# Adafruit_Feather_M0_Basic_rev_C.net
KiCad netlist of a schematic drawn in EAGLE
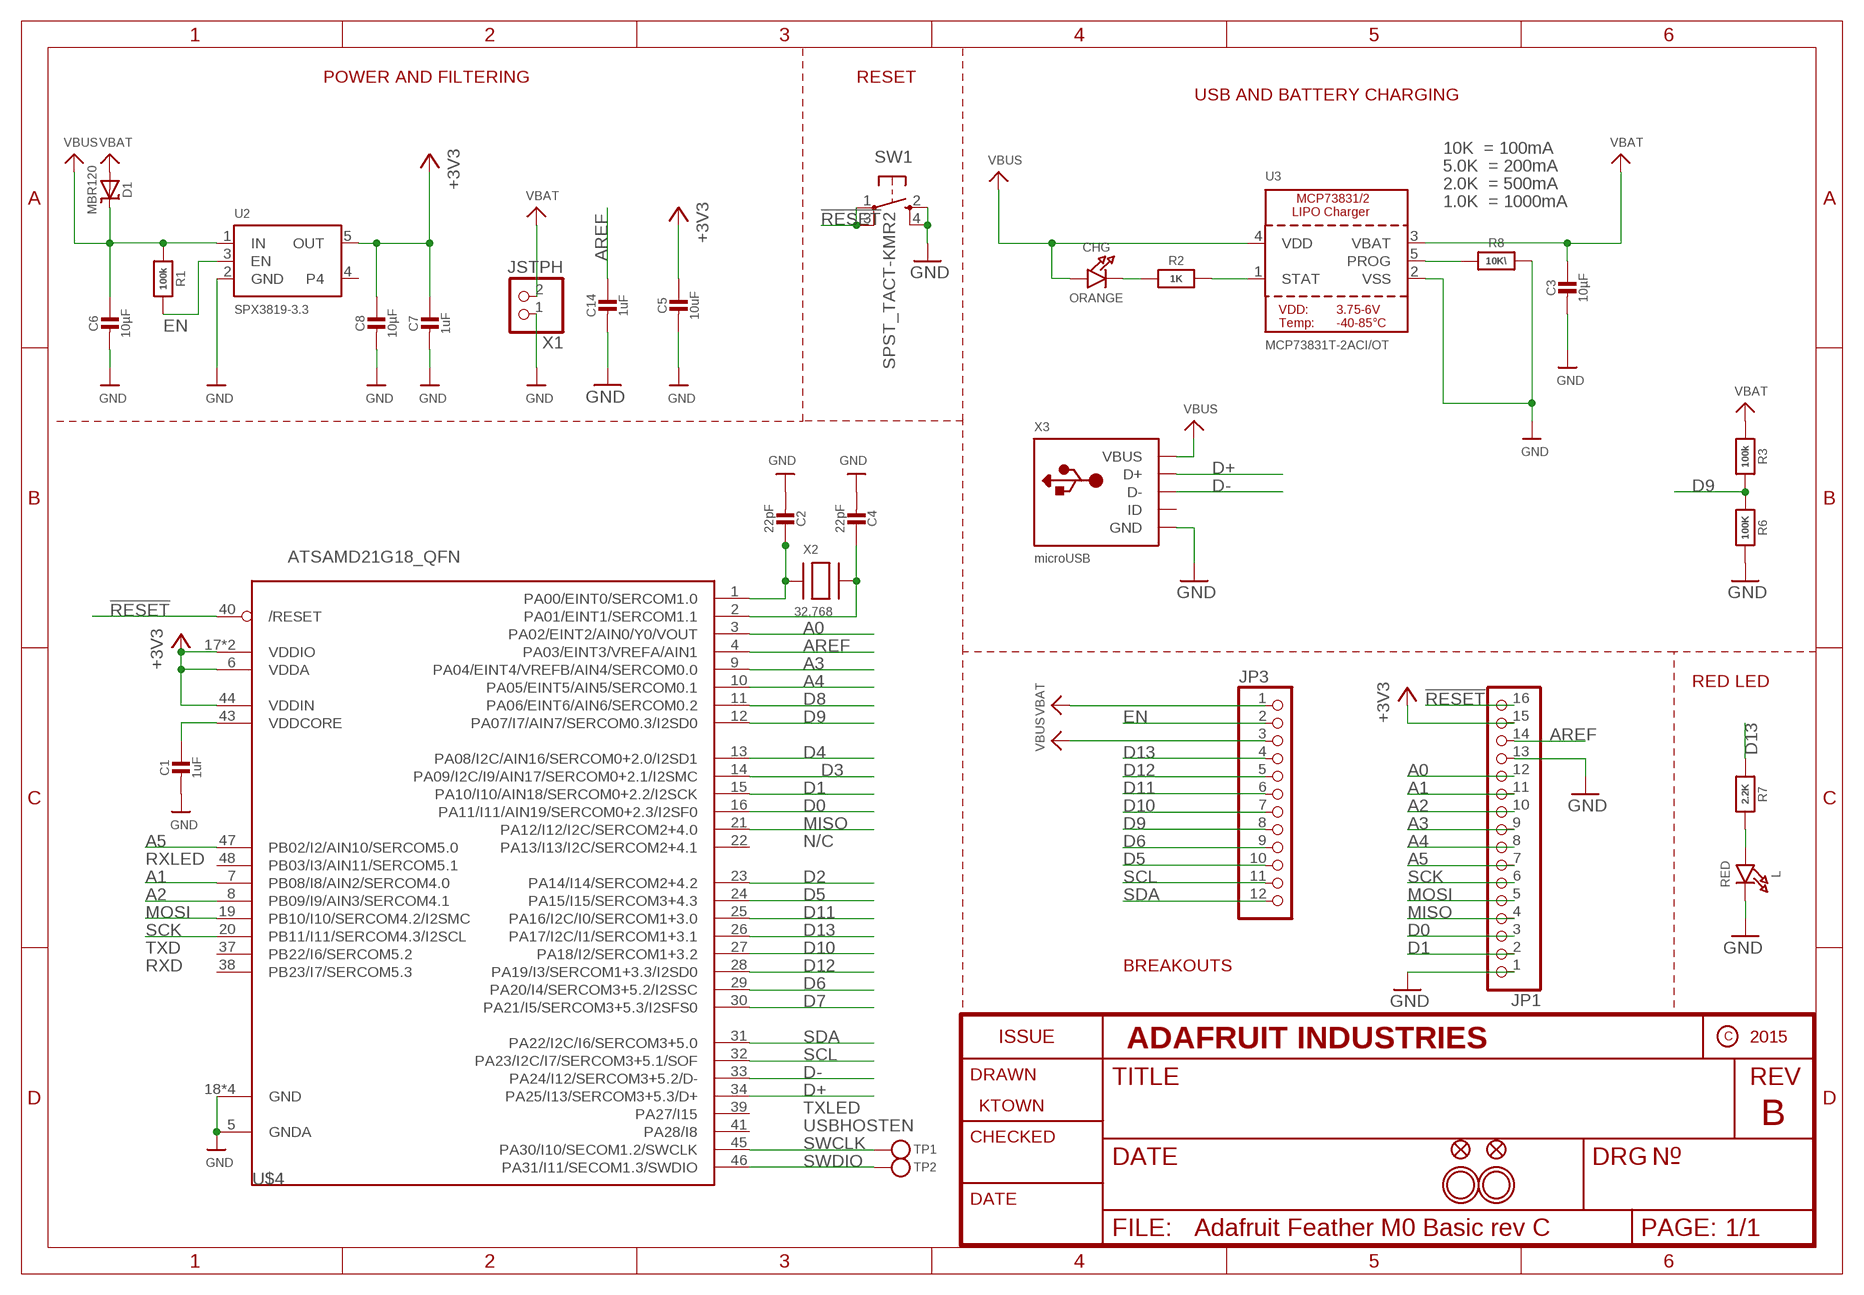
[diagram p0: schematic, sheet 1]

(export (version "E")
  (design (tool "Eeschema 10.0.6"))
  (components
    (comp (ref "C1")
      (value "1uF")
      (footprint "eagle-import:0603-NO")
      (libsource (lib "eagle-import") (part "CAP_CERAMIC0603_NO"))
    )
    (comp (ref "C2")
      (value "22pF")
      (footprint "eagle-import:0603-NO")
      (libsource (lib "eagle-import") (part "CAP_CERAMIC0603_NO"))
    )
    (comp (ref "C3")
      (value "10µF")
      (footprint "eagle-import:0805-NO")
      (libsource (lib "eagle-import") (part "CAP_CERAMIC0805-NOOUTLINE"))
    )
    (comp (ref "C4")
      (value "22pF")
      (footprint "eagle-import:0603-NO")
      (libsource (lib "eagle-import") (part "CAP_CERAMIC0603_NO"))
    )
    (comp (ref "C5")
      (value "10uF")
      (footprint "eagle-import:0805-NO")
      (libsource (lib "eagle-import") (part "CAP_CERAMIC0805-NOOUTLINE"))
    )
    (comp (ref "C6")
      (value "10µF")
      (footprint "eagle-import:0805-NO")
      (libsource (lib "eagle-import") (part "CAP_CERAMIC0805-NOOUTLINE"))
    )
    (comp (ref "C7")
      (value "1uF")
      (footprint "eagle-import:0603-NO")
      (libsource (lib "eagle-import") (part "CAP_CERAMIC0603_NO"))
    )
    (comp (ref "C8")
      (value "10µF")
      (footprint "eagle-import:0805-NO")
      (libsource (lib "eagle-import") (part "CAP_CERAMIC0805-NOOUTLINE"))
    )
    (comp (ref "C14")
      (value "1uF")
      (footprint "eagle-import:0603-NO")
      (libsource (lib "eagle-import") (part "CAP_CERAMIC0603_NO"))
    )
    (comp (ref "CHG")
      (value "ORANGE")
      (footprint "eagle-import:CHIPLED_0805_NOOUTLINE")
      (libsource (lib "eagle-import") (part "LED0805_NOOUTLINE"))
    )
    (comp (ref "D1")
      (value "MBR120")
      (footprint "eagle-import:SOD-123")
      (libsource (lib "eagle-import") (part "DIODE-SCHOTTKYSOD-123"))
    )
    (comp (ref "JP1")
      (value "HEADER-1X16ROUND")
      (footprint "eagle-import:1X16_ROUND")
      (libsource (lib "eagle-import") (part "HEADER-1X16ROUND"))
    )
    (comp (ref "JP3")
      (value "HEADER-1X12")
      (footprint "eagle-import:1X12_ROUND")
      (libsource (lib "eagle-import") (part "HEADER-1X12"))
    )
    (comp (ref "L")
      (value "RED")
      (footprint "eagle-import:CHIPLED_0805_NOOUTLINE")
      (libsource (lib "eagle-import") (part "LED0805_NOOUTLINE"))
    )
    (comp (ref "R1")
      (value "100k")
      (footprint "eagle-import:0603-NO")
      (libsource (lib "eagle-import") (part "RESISTOR_0603_NOOUT"))
    )
    (comp (ref "R2")
      (value "1K")
      (footprint "eagle-import:0603-NO")
      (libsource (lib "eagle-import") (part "RESISTOR_0603_NOOUT"))
    )
    (comp (ref "R3")
      (value "100k")
      (footprint "eagle-import:0603-NO")
      (libsource (lib "eagle-import") (part "RESISTOR_0603_NOOUT"))
    )
    (comp (ref "R6")
      (value "100K")
      (footprint "eagle-import:0603-NO")
      (libsource (lib "eagle-import") (part "RESISTOR_0603_NOOUT"))
    )
    (comp (ref "R7")
      (value "2.2K")
      (footprint "eagle-import:0603-NO")
      (libsource (lib "eagle-import") (part "RESISTOR_0603_NOOUT"))
    )
    (comp (ref "R8")
      (value "10K\\")
      (footprint "eagle-import:0603-NO")
      (libsource (lib "eagle-import") (part "RESISTOR_0603_NOOUT"))
    )
    (comp (ref "SW1")
      (value "SPST_TACT-KMR2")
      (footprint "eagle-import:KMR2")
      (libsource (lib "eagle-import") (part "SPST_TACT-KMR2"))
    )
    (comp (ref "TP1")
      (value "TESTPOINTROUND1.5MM")
      (footprint "eagle-import:TESTPOINT_ROUND_1.5MM")
      (libsource (lib "eagle-import") (part "TESTPOINTROUND1.5MM"))
    )
    (comp (ref "TP2")
      (value "TESTPOINTROUND1.5MM")
      (footprint "eagle-import:TESTPOINT_ROUND_1.5MM")
      (libsource (lib "eagle-import") (part "TESTPOINTROUND1.5MM"))
    )
    (comp (ref "U$4")
      (value "ATSAMD21G18_QFN")
      (footprint "eagle-import:TQFN48_7MM")
      (libsource (lib "eagle-import") (part "ATSAMD21J_QFN"))
    )
    (comp (ref "U$31")
      (value "MOUNTINGHOLE2.5")
      (footprint "eagle-import:MOUNTINGHOLE_2.5_PLATED")
      (libsource (lib "eagle-import") (part "MOUNTINGHOLE2.5"))
    )
    (comp (ref "U$32")
      (value "MOUNTINGHOLE2.5")
      (footprint "eagle-import:MOUNTINGHOLE_2.5_PLATED")
      (libsource (lib "eagle-import") (part "MOUNTINGHOLE2.5"))
    )
    (comp (ref "U$34")
      (value "FIDUCIAL\"\"")
      (footprint "eagle-import:FIDUCIAL_1MM")
      (libsource (lib "eagle-import") (part "FIDUCIAL{dblquote}{dblquote}"))
    )
    (comp (ref "U$35")
      (value "FIDUCIAL\"\"")
      (footprint "eagle-import:FIDUCIAL_1MM")
      (libsource (lib "eagle-import") (part "FIDUCIAL{dblquote}{dblquote}"))
    )
    (comp (ref "U2")
      (value "SPX3819-3.3")
      (footprint "eagle-import:SOT23-5")
      (libsource (lib "eagle-import") (part "VREG_SOT23-5"))
    )
    (comp (ref "U3")
      (value "MCP73831T-2ACI/OT")
      (footprint "eagle-import:SOT23-5")
      (libsource (lib "eagle-import") (part "MCP73831/2"))
    )
    (comp (ref "X1")
      (value "JSTPH")
      (footprint "eagle-import:JSTPH2")
      (libsource (lib "eagle-import") (part "CON_JST_PH_2PIN"))
    )
    (comp (ref "X2")
      (value "32.768")
      (footprint "eagle-import:XTAL3215")
      (libsource (lib "eagle-import") (part "XTAL-3.2X1.5"))
    )
    (comp (ref "X3")
      (value "microUSB")
      (footprint "eagle-import:4UCONN_20329_V2")
      (libsource (lib "eagle-import") (part "USB_MICRO_20329_V2"))
    )
  )
  (nets
    (net (code "1") (name "+3V3") (class "Default")
      (node (ref "C5") (pin "1") (pinfunction "1_1") (pintype "passive"))
      (node (ref "C7") (pin "1") (pinfunction "1_1") (pintype "passive"))
      (node (ref "C8") (pin "1") (pinfunction "1_1") (pintype "passive"))
      (node (ref "JP1") (pin "15") (pinfunction "15_15") (pintype "passive"))
      (node (ref "U$4") (pin "17") (pinfunction "VDDIO_17") (pintype "power_in"))
      (node (ref "U$4") (pin "36") (pinfunction "VDDIO_36") (pintype "power_in"))
      (node (ref "U$4") (pin "44") (pinfunction "VDDIN_44") (pintype "power_in"))
      (node (ref "U$4") (pin "6") (pinfunction "VDDA_6") (pintype "power_in"))
      (node (ref "U2") (pin "5") (pinfunction "OUT_5") (pintype "power_in"))
    )
    (net (code "2") (name "/A0") (class "Default")
      (node (ref "JP1") (pin "12") (pinfunction "12_12") (pintype "passive"))
      (node (ref "U$4") (pin "3") (pinfunction "PA02/EINT2/AIN0/Y0/VOUT_3") (pintype "bidirectional"))
    )
    (net (code "3") (name "/A1") (class "Default")
      (node (ref "JP1") (pin "11") (pinfunction "11_11") (pintype "passive"))
      (node (ref "U$4") (pin "7") (pinfunction "PB08/I8/AIN2/SERCOM4.0_7") (pintype "bidirectional"))
    )
    (net (code "4") (name "/A2") (class "Default")
      (node (ref "JP1") (pin "10") (pinfunction "10_10") (pintype "passive"))
      (node (ref "U$4") (pin "8") (pinfunction "PB09/I9/AIN3/SERCOM4.1_8") (pintype "bidirectional"))
    )
    (net (code "5") (name "/A3") (class "Default")
      (node (ref "JP1") (pin "9") (pinfunction "9_9") (pintype "passive"))
      (node (ref "U$4") (pin "9") (pinfunction "PA04/EINT4/VREFB/AIN4/SERCOM0.0_9") (pintype "bidirectional"))
    )
    (net (code "6") (name "/A4") (class "Default")
      (node (ref "JP1") (pin "8") (pinfunction "8_8") (pintype "passive"))
      (node (ref "U$4") (pin "10") (pinfunction "PA05/EINT5/AIN5/SERCOM0.1_10") (pintype "bidirectional"))
    )
    (net (code "7") (name "/A5") (class "Default")
      (node (ref "JP1") (pin "7") (pinfunction "7_7") (pintype "passive"))
      (node (ref "U$4") (pin "47") (pinfunction "PB02/I2/AIN10/SERCOM5.0_47") (pintype "bidirectional"))
    )
    (net (code "8") (name "/AREF") (class "Default")
      (node (ref "C14") (pin "1") (pinfunction "1_1") (pintype "passive"))
      (node (ref "JP1") (pin "14") (pinfunction "14_14") (pintype "passive"))
      (node (ref "U$4") (pin "4") (pinfunction "PA03/EINT3/VREFA/AIN1_4") (pintype "bidirectional"))
    )
    (net (code "9") (name "/D+") (class "Default")
      (node (ref "U$4") (pin "34") (pinfunction "PA25/I13/SERCOM3+5.3/D+_34") (pintype "bidirectional"))
      (node (ref "X3") (pin "D+") (pinfunction "D+_D+") (pintype "bidirectional"))
    )
    (net (code "10") (name "/D-") (class "Default")
      (node (ref "U$4") (pin "33") (pinfunction "PA24/I12/SERCOM3+5.2/D-_33") (pintype "bidirectional"))
      (node (ref "X3") (pin "D-") (pinfunction "D-_D-") (pintype "bidirectional"))
    )
    (net (code "11") (name "/D0") (class "Default")
      (node (ref "JP1") (pin "3") (pinfunction "3_3") (pintype "passive"))
      (node (ref "U$4") (pin "16") (pinfunction "PA11/I11/AIN19/SERCOM0+2.3/I2SF0_16") (pintype "bidirectional"))
    )
    (net (code "12") (name "/D1") (class "Default")
      (node (ref "JP1") (pin "2") (pinfunction "2_2") (pintype "passive"))
      (node (ref "U$4") (pin "15") (pinfunction "PA10/I10/AIN18/SERCOM0+2.2/I2SCK_15") (pintype "bidirectional"))
    )
    (net (code "13") (name "/D2") (class "Default")
      (node (ref "U$4") (pin "23") (pinfunction "PA14/I14/SERCOM2+4.2_23") (pintype "bidirectional"))
    )
    (net (code "14") (name "/D3") (class "Default")
      (node (ref "U$4") (pin "14") (pinfunction "PA09/I2C/I9/AIN17/SERCOM0+2.1/I2SMC_14") (pintype "bidirectional"))
    )
    (net (code "15") (name "/D4") (class "Default")
      (node (ref "U$4") (pin "13") (pinfunction "PA08/I2C/AIN16/SERCOM0+2.0/I2SD1_13") (pintype "bidirectional"))
    )
    (net (code "16") (name "/D5") (class "Default")
      (node (ref "JP3") (pin "10") (pinfunction "10_10") (pintype "passive"))
      (node (ref "U$4") (pin "24") (pinfunction "PA15/I15/SERCOM3+4.3_24") (pintype "bidirectional"))
    )
    (net (code "17") (name "/D6") (class "Default")
      (node (ref "JP3") (pin "9") (pinfunction "9_9") (pintype "passive"))
      (node (ref "U$4") (pin "29") (pinfunction "PA20/I4/SERCOM3+5.2/I2SSC_29") (pintype "bidirectional"))
    )
    (net (code "18") (name "/D7") (class "Default")
      (node (ref "U$4") (pin "30") (pinfunction "PA21/I5/SERCOM3+5.3/I2SFS0_30") (pintype "bidirectional"))
    )
    (net (code "19") (name "/D8") (class "Default")
      (node (ref "U$4") (pin "11") (pinfunction "PA06/EINT6/AIN6/SERCOM0.2_11") (pintype "bidirectional"))
    )
    (net (code "20") (name "/D9") (class "Default")
      (node (ref "JP3") (pin "8") (pinfunction "8_8") (pintype "passive"))
      (node (ref "R3") (pin "2") (pinfunction "2_2") (pintype "passive"))
      (node (ref "R6") (pin "1") (pinfunction "1_1") (pintype "passive"))
      (node (ref "U$4") (pin "12") (pinfunction "PA07/I7/AIN7/SERCOM0.3/I2SD0_12") (pintype "bidirectional"))
    )
    (net (code "21") (name "/D10") (class "Default")
      (node (ref "JP3") (pin "7") (pinfunction "7_7") (pintype "passive"))
      (node (ref "U$4") (pin "27") (pinfunction "PA18/I2/SERCOM1+3.2_27") (pintype "bidirectional"))
    )
    (net (code "22") (name "/D11") (class "Default")
      (node (ref "JP3") (pin "6") (pinfunction "6_6") (pintype "passive"))
      (node (ref "U$4") (pin "25") (pinfunction "PA16/I2C/I0/SERCOM1+3.0_25") (pintype "bidirectional"))
    )
    (net (code "23") (name "/D12") (class "Default")
      (node (ref "JP3") (pin "5") (pinfunction "5_5") (pintype "passive"))
      (node (ref "U$4") (pin "28") (pinfunction "PA19/I3/SERCOM1+3.3/I2SD0_28") (pintype "bidirectional"))
    )
    (net (code "24") (name "/D13") (class "Default")
      (node (ref "JP3") (pin "4") (pinfunction "4_4") (pintype "passive"))
      (node (ref "R7") (pin "1") (pinfunction "1_1") (pintype "passive"))
      (node (ref "U$4") (pin "26") (pinfunction "PA17/I2C/I1/SERCOM1+3.1_26") (pintype "bidirectional"))
    )
    (net (code "25") (name "/EN") (class "Default")
      (node (ref "JP3") (pin "2") (pinfunction "2_2") (pintype "passive"))
      (node (ref "R1") (pin "2") (pinfunction "2_2") (pintype "passive"))
      (node (ref "U2") (pin "3") (pinfunction "EN_3") (pintype "input"))
    )
    (net (code "26") (name "/MISO") (class "Default")
      (node (ref "JP1") (pin "4") (pinfunction "4_4") (pintype "passive"))
      (node (ref "U$4") (pin "21") (pinfunction "PA12/I12/I2C/SERCOM2+4.0_21") (pintype "bidirectional"))
    )
    (net (code "27") (name "/MOSI") (class "Default")
      (node (ref "JP1") (pin "5") (pinfunction "5_5") (pintype "passive"))
      (node (ref "U$4") (pin "19") (pinfunction "PB10/I10/SERCOM4.2/I2SMC_19") (pintype "bidirectional"))
    )
    (net (code "28") (name "/SCK") (class "Default")
      (node (ref "JP1") (pin "6") (pinfunction "6_6") (pintype "passive"))
      (node (ref "U$4") (pin "20") (pinfunction "PB11/I11/SERCOM4.3/I2SCL_20") (pintype "bidirectional"))
    )
    (net (code "29") (name "/SCL") (class "Default")
      (node (ref "JP3") (pin "11") (pinfunction "11_11") (pintype "passive"))
      (node (ref "U$4") (pin "32") (pinfunction "PA23/I2C/I7/SERCOM3+5.1/SOF_32") (pintype "bidirectional"))
    )
    (net (code "30") (name "/SDA") (class "Default")
      (node (ref "JP3") (pin "12") (pinfunction "12_12") (pintype "passive"))
      (node (ref "U$4") (pin "31") (pinfunction "PA22/I2C/I6/SERCOM3+5.0_31") (pintype "bidirectional"))
    )
    (net (code "31") (name "/SWCLK") (class "Default")
      (node (ref "TP1") (pin "P$1") (pinfunction "P$1_P$1") (pintype "bidirectional"))
      (node (ref "U$4") (pin "45") (pinfunction "PA30/I10/SECOM1.2/SWCLK_45") (pintype "bidirectional"))
    )
    (net (code "32") (name "/SWDIO") (class "Default")
      (node (ref "TP2") (pin "P$1") (pinfunction "P$1_P$1") (pintype "bidirectional"))
      (node (ref "U$4") (pin "46") (pinfunction "PA31/I11/SECOM1.3/SWDIO_46") (pintype "bidirectional"))
    )
    (net (code "33") (name "/~{RESET}") (class "Default")
      (node (ref "JP1") (pin "16") (pinfunction "16_16") (pintype "passive"))
      (node (ref "SW1") (pin "1") (pinfunction "P_1") (pintype "passive"))
      (node (ref "SW1") (pin "3") (pinfunction "P1_3") (pintype "passive"))
      (node (ref "U$4") (pin "40") (pinfunction "/RESET_40") (pintype "bidirectional"))
    )
    (net (code "34") (name "GND") (class "Default")
      (node (ref "C1") (pin "2") (pinfunction "2_2") (pintype "passive"))
      (node (ref "C14") (pin "2") (pinfunction "2_2") (pintype "passive"))
      (node (ref "C2") (pin "2") (pinfunction "2_2") (pintype "passive"))
      (node (ref "C3") (pin "2") (pinfunction "2_2") (pintype "passive"))
      (node (ref "C4") (pin "2") (pinfunction "2_2") (pintype "passive"))
      (node (ref "C5") (pin "2") (pinfunction "2_2") (pintype "passive"))
      (node (ref "C6") (pin "2") (pinfunction "2_2") (pintype "passive"))
      (node (ref "C7") (pin "2") (pinfunction "2_2") (pintype "passive"))
      (node (ref "C8") (pin "2") (pinfunction "2_2") (pintype "passive"))
      (node (ref "JP1") (pin "1") (pinfunction "1_1") (pintype "passive"))
      (node (ref "JP1") (pin "13") (pinfunction "13_13") (pintype "passive"))
      (node (ref "L") (pin "C") (pinfunction "C_C") (pintype "passive"))
      (node (ref "R6") (pin "2") (pinfunction "2_2") (pintype "passive"))
      (node (ref "R8") (pin "2") (pinfunction "2_2") (pintype "passive"))
      (node (ref "SW1") (pin "2") (pinfunction "S_2") (pintype "passive"))
      (node (ref "SW1") (pin "4") (pinfunction "S1_4") (pintype "passive"))
      (node (ref "U$4") (pin "18") (pinfunction "GND_18") (pintype "power_in"))
      (node (ref "U$4") (pin "35") (pinfunction "GND_35") (pintype "power_in"))
      (node (ref "U$4") (pin "42") (pinfunction "GND_42") (pintype "power_in"))
      (node (ref "U$4") (pin "5") (pinfunction "GNDA_5") (pintype "power_in"))
      (node (ref "U$4") (pin "THERMAL") (pinfunction "GND_THERMAL") (pintype "power_in"))
      (node (ref "U2") (pin "2") (pinfunction "GND_2") (pintype "power_in"))
      (node (ref "U3") (pin "2") (pinfunction "VSS_2") (pintype "power_in"))
      (node (ref "X1") (pin "1") (pinfunction "1_1") (pintype "passive"))
      (node (ref "X3") (pin "BASE@1") (pinfunction "GND_BASE@1") (pintype "power_in"))
      (node (ref "X3") (pin "BASE@2") (pinfunction "GND_BASE@2") (pintype "power_in"))
      (node (ref "X3") (pin "GND") (pinfunction "GND_GND") (pintype "power_in"))
      (node (ref "X3") (pin "SPRT@1") (pinfunction "GND_SPRT@1") (pintype "power_in"))
      (node (ref "X3") (pin "SPRT@2") (pinfunction "GND_SPRT@2") (pintype "power_in"))
      (node (ref "X3") (pin "SPRT@3") (pinfunction "GND_SPRT@3") (pintype "power_in"))
      (node (ref "X3") (pin "SPRT@4") (pinfunction "GND_SPRT@4") (pintype "power_in"))
    )
    (net (code "35") (name "Net-(CHG-PadC)") (class "Default")
      (node (ref "CHG") (pin "C") (pinfunction "C_C") (pintype "passive"))
      (node (ref "R2") (pin "1") (pinfunction "1_1") (pintype "passive"))
    )
    (net (code "36") (name "Net-(L-PadA)") (class "Default")
      (node (ref "L") (pin "A") (pinfunction "A_A") (pintype "passive"))
      (node (ref "R7") (pin "2") (pinfunction "2_2") (pintype "passive"))
    )
    (net (code "37") (name "Net-(U$4-PA00{slash}EINT0{slash}SERCOM1.0)") (class "Default")
      (node (ref "C2") (pin "1") (pinfunction "1_1") (pintype "passive"))
      (node (ref "U$4") (pin "1") (pinfunction "PA00/EINT0/SERCOM1.0_1") (pintype "bidirectional"))
      (node (ref "X2") (pin "P$1") (pinfunction "P$1_P$1") (pintype "bidirectional"))
    )
    (net (code "38") (name "Net-(U$4-PA01{slash}EINT1{slash}SERCOM1.1)") (class "Default")
      (node (ref "C4") (pin "1") (pinfunction "1_1") (pintype "passive"))
      (node (ref "U$4") (pin "2") (pinfunction "PA01/EINT1/SERCOM1.1_2") (pintype "bidirectional"))
      (node (ref "X2") (pin "P$2") (pinfunction "P$2_P$2") (pintype "bidirectional"))
    )
    (net (code "39") (name "Net-(U$4-VDDCORE)") (class "Default")
      (node (ref "C1") (pin "1") (pinfunction "1_1") (pintype "passive"))
      (node (ref "U$4") (pin "43") (pinfunction "VDDCORE_43") (pintype "power_in"))
    )
    (net (code "40") (name "Net-(U3-PROG)") (class "Default")
      (node (ref "R8") (pin "1") (pinfunction "1_1") (pintype "passive"))
      (node (ref "U3") (pin "5") (pinfunction "PROG_5") (pintype "input"))
    )
    (net (code "41") (name "Net-(U3-STAT)") (class "Default")
      (node (ref "R2") (pin "2") (pinfunction "2_2") (pintype "passive"))
      (node (ref "U3") (pin "1") (pinfunction "STAT_1") (pintype "output"))
    )
    (net (code "42") (name "VBAT") (class "Default")
      (node (ref "C3") (pin "1") (pinfunction "1_1") (pintype "passive"))
      (node (ref "D1") (pin "A") (pinfunction "A_A") (pintype "passive"))
      (node (ref "JP3") (pin "1") (pinfunction "1_1") (pintype "passive"))
      (node (ref "R3") (pin "1") (pinfunction "1_1") (pintype "passive"))
      (node (ref "U3") (pin "3") (pinfunction "VBAT_3") (pintype "power_in"))
      (node (ref "X1") (pin "2") (pinfunction "2_2") (pintype "passive"))
    )
    (net (code "43") (name "VBUS") (class "Default")
      (node (ref "C6") (pin "1") (pinfunction "1_1") (pintype "passive"))
      (node (ref "CHG") (pin "A") (pinfunction "A_A") (pintype "passive"))
      (node (ref "D1") (pin "C") (pinfunction "C_C") (pintype "passive"))
      (node (ref "JP3") (pin "3") (pinfunction "3_3") (pintype "passive"))
      (node (ref "R1") (pin "1") (pinfunction "1_1") (pintype "passive"))
      (node (ref "U2") (pin "1") (pinfunction "IN_1") (pintype "power_in"))
      (node (ref "U3") (pin "4") (pinfunction "VDD_4") (pintype "power_in"))
      (node (ref "X3") (pin "VBUS") (pinfunction "VBUS_VBUS") (pintype "power_in"))
    )
    (net (code "44") (name "unconnected-(U$4-PA13{slash}I13{slash}I2C{slash}SERCOM2+4.1-Pad22)") (class "Default")
      (node (ref "U$4") (pin "22") (pinfunction "PA13/I13/I2C/SERCOM2+4.1_22") (pintype "bidirectional"))
    )
    (net (code "45") (name "unconnected-(U$4-PA27{slash}I15-Pad39)") (class "Default")
      (node (ref "U$4") (pin "39") (pinfunction "PA27/I15_39") (pintype "bidirectional"))
    )
    (net (code "46") (name "unconnected-(U$4-PA28{slash}I8-Pad41)") (class "Default")
      (node (ref "U$4") (pin "41") (pinfunction "PA28/I8_41") (pintype "bidirectional"))
    )
    (net (code "47") (name "unconnected-(U$4-PB03{slash}I3{slash}AIN11{slash}SERCOM5.1-Pad48)") (class "Default")
      (node (ref "U$4") (pin "48") (pinfunction "PB03/I3/AIN11/SERCOM5.1_48") (pintype "bidirectional"))
    )
    (net (code "48") (name "unconnected-(U$4-PB22{slash}I6{slash}SERCOM5.2-Pad37)") (class "Default")
      (node (ref "U$4") (pin "37") (pinfunction "PB22/I6/SERCOM5.2_37") (pintype "bidirectional"))
    )
    (net (code "49") (name "unconnected-(U$4-PB23{slash}I7{slash}SERCOM5.3-Pad38)") (class "Default")
      (node (ref "U$4") (pin "38") (pinfunction "PB23/I7/SERCOM5.3_38") (pintype "bidirectional"))
    )
    (net (code "50") (name "unconnected-(U2-P4-Pad4)") (class "Default")
      (node (ref "U2") (pin "4") (pinfunction "P4_4") (pintype "bidirectional"))
    )
    (net (code "51") (name "unconnected-(X3-PadID)") (class "Default")
      (node (ref "X3") (pin "ID") (pinfunction "ID_ID") (pintype "bidirectional"))
    )
  )
)
